# NRF.net
KiCad netlist of a schematic drawn in Altium Designer
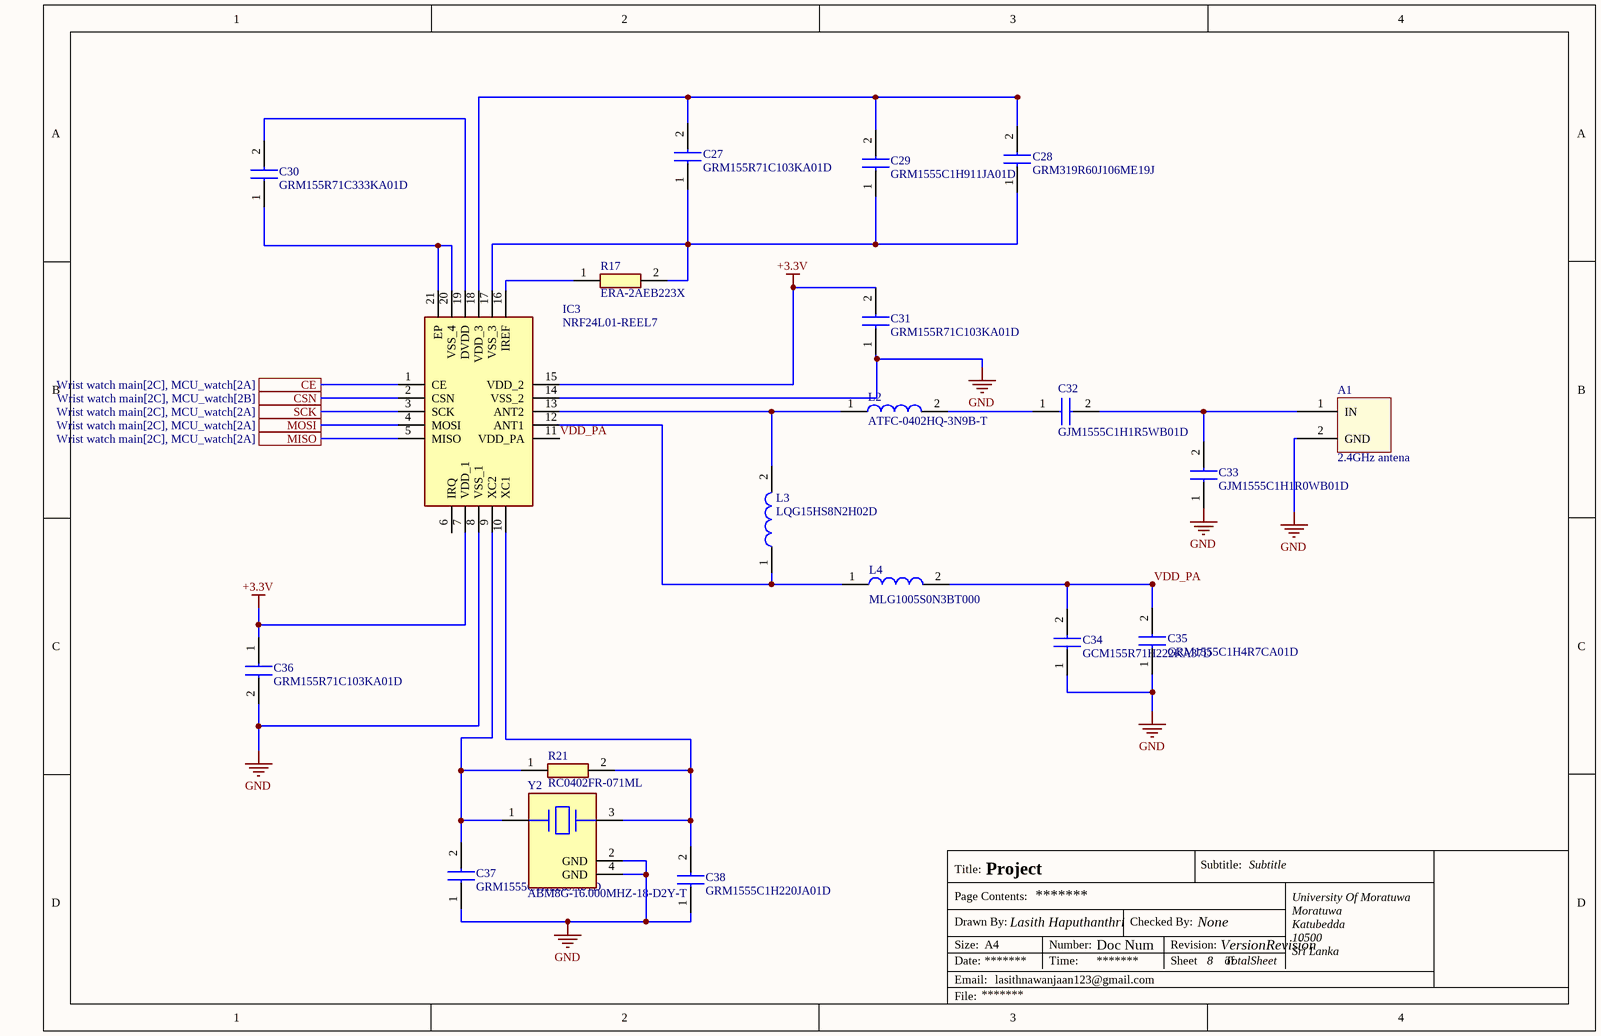
[diagram p0: NRF.SchDoc]

(export (version "E")
  (design (tool "Eeschema 10.0.6"))
  (components
    (comp (ref "A1")
      (value "2.4GHz antena")
      (footprint "Antena")
      (libsource (lib "Schlib1") (part "2.4GHz antena"))
    )
    (comp (ref "C27")
      (value "GRM155R71C103KA01D")
      (footprint "SamacSys:CAPC1005X55N")
      (description "Capacitor")
      (fields (field (name "MOUSER PART NUMBER") "81-GRM36X103K16"))
      (libsource (lib "*") (part "GRM155R71C103KA01D"))
    )
    (comp (ref "C28")
      (value "GRM319R60J106ME19J")
      (footprint "SamacSys:CAPC3216X95N")
      (description "Capacitor")
      (fields (field (name "MOUSER PART NUMBER") "81-GRM319R60J106ME9J"))
      (libsource (lib "*") (part "GRM319R60J106ME19J"))
    )
    (comp (ref "C29")
      (value "GRM1555C1H911JA01D")
      (footprint "SamacSys:CAPC1005X55N")
      (description "Capacitor")
      (fields (field (name "MOUSER PART NUMBER") "81-GRM1555C1H911JA1D"))
      (libsource (lib "*") (part "GRM1555C1H911JA01D"))
    )
    (comp (ref "C30")
      (value "GRM155R71C333KA01D")
      (footprint "SamacSys:CAPC1005X55N")
      (description "Capacitor")
      (libsource (lib "*") (part "GRM155R71C333KA01D"))
    )
    (comp (ref "C31")
      (value "GRM155R71C103KA01D")
      (footprint "SamacSys:CAPC1005X55N")
      (description "Capacitor")
      (fields (field (name "MOUSER PART NUMBER") "81-GRM36X103K16"))
      (libsource (lib "*") (part "GRM155R71C103KA01D"))
    )
    (comp (ref "C32")
      (value "GJM1555C1H1R5WB01D")
      (footprint "SamacSys:CAPC1005X55N")
      (description "Capacitor")
      (fields (field (name "MOUSER PART NUMBER") "81-GJM1555C1H1R5WB1D"))
      (libsource (lib "*") (part "GJM1555C1H1R5WB01D"))
    )
    (comp (ref "C33")
      (value "GJM1555C1H1R0WB01D")
      (footprint "SamacSys:CAPC1005X55N")
      (description "Capacitor")
      (fields (field (name "MOUSER PART NUMBER") "81-GJM1555C1H1R0WB1D"))
      (libsource (lib "*") (part "GJM1555C1H1R0WB01D"))
    )
    (comp (ref "C34")
      (value "GCM155R71H222KA37D")
      (footprint "SamacSys:CAPC1005X55N")
      (description "Capacitor")
      (fields (field (name "MOUSER PART NUMBER") "81-GCM155R71H222K37D"))
      (libsource (lib "*") (part "GCM155R71H222KA37D"))
    )
    (comp (ref "C35")
      (value "GRM1555C1H4R7CA01D")
      (footprint "SamacSys:CAPC1005X55N")
      (description "Capacitor")
      (fields (field (name "MOUSER PART NUMBER") "81-GRM1555C1H4R7CA1D"))
      (libsource (lib "*") (part "GRM1555C1H4R7CA01D"))
    )
    (comp (ref "C36")
      (value "GRM155R71C103KA01D")
      (footprint "SamacSys:CAPC1005X55N")
      (description "Capacitor")
      (fields (field (name "MOUSER PART NUMBER") "81-GRM36X103K16"))
      (libsource (lib "*") (part "GRM155R71C103KA01D"))
    )
    (comp (ref "C37")
      (value "GRM1555C1H220JA01D")
      (footprint "SamacSys:CAPC1005X55N")
      (description "Capacitor")
      (fields (field (name "MOUSER PART NUMBER") "81-GRM1555C1H220JA1D"))
      (libsource (lib "*") (part "GRM1555C1H220JA01D"))
    )
    (comp (ref "C38")
      (value "GRM1555C1H220JA01D")
      (footprint "SamacSys:CAPC1005X55N")
      (description "Capacitor")
      (fields (field (name "MOUSER PART NUMBER") "81-GRM1555C1H220JA1D"))
      (libsource (lib "*") (part "GRM1555C1H220JA01D"))
    )
    (comp (ref "IC3")
      (value "NRF24L01-REEL7")
      (footprint "SamacSys:QFN50P400X400X80-21N-D")
      (description "Integrated Circuit")
      (fields (field (name "MOUSER PART NUMBER") "949-NRF24L01-REEL7"))
      (libsource (lib "*") (part "NRF24L01-REEL7"))
    )
    (comp (ref "L2")
      (value "ATFC-0402HQ-3N9B-T")
      (footprint "SamacSys:INDC1005X37N")
      (description "Inductor")
      (libsource (lib "*") (part "ATFC-0402HQ-3N9B-T"))
    )
    (comp (ref "L3")
      (value "LQG15HS8N2H02D")
      (footprint "SamacSys:LQG15WH0N7B02D")
      (description "Inductor")
      (fields (field (name "MOUSER PART NUMBER") "81-LQG15HS8N2H02D"))
      (libsource (lib "*") (part "LQG15HS8N2H02D"))
    )
    (comp (ref "L4")
      (value "MLG1005S0N3BT000")
      (footprint "SamacSys:MLG1005")
      (description "Inductor")
      (fields (field (name "MOUSER PART NUMBER") "810-MLG1005S0N3BT000"))
      (libsource (lib "*") (part "MLG1005S0N3BT000"))
    )
    (comp (ref "R17")
      (value "ERA-2AEB223X")
      (footprint "SamacSys:ERA2AED122X")
      (description "Resistor")
      (fields (field (name "MOUSER PART NUMBER") "667-ERA-2AEB223X"))
      (libsource (lib "*") (part "ERA-2AEB223X"))
    )
    (comp (ref "R21")
      (value "RC0402FR-071ML")
      (footprint "SamacSys:RESC1005X40N")
      (description "Resistor")
      (fields (field (name "MOUSER PART NUMBER") "603-RC0402FR-071ML"))
      (libsource (lib "*") (part "RC0402FR-071ML"))
    )
    (comp (ref "Y2")
      (value "ABM8G-16.000MHZ-18-D2Y-T")
      (footprint "FP-ABM8G-MFG")
      (description "Crystal 12MHz ±20ppm (Tol) ±30ppm (Stability) 18pF FUND 120Ω 4-Pin SMD T/R")
      (fields (field (name "TOLERANCE") "20ppm"))
      (libsource (lib "Altium Content Vault") (part "48e526d86b7f2615d98721063c72f49"))
    )
  )
  (nets
    (net (code "1") (name "+3.3V") (class "Default")
      (node (ref "C31") (pin "2") (pinfunction "2_2") (pintype "passive"))
      (node (ref "C36") (pin "1") (pinfunction "1_1") (pintype "passive"))
      (node (ref "IC3") (pin "15") (pinfunction "VDD_2_15") (pintype "passive"))
      (node (ref "IC3") (pin "7") (pinfunction "VDD_1_7") (pintype "passive"))
    )
    (net (code "2") (name "/CE") (class "Default")
      (node (ref "IC3") (pin "1") (pinfunction "CE_1") (pintype "passive"))
    )
    (net (code "3") (name "/CSN") (class "Default")
      (node (ref "IC3") (pin "2") (pinfunction "CSN_2") (pintype "passive"))
    )
    (net (code "4") (name "/MISO") (class "Default")
      (node (ref "IC3") (pin "5") (pinfunction "MISO_5") (pintype "passive"))
    )
    (net (code "5") (name "/MOSI") (class "Default")
      (node (ref "IC3") (pin "4") (pinfunction "MOSI_4") (pintype "passive"))
    )
    (net (code "6") (name "/SCK") (class "Default")
      (node (ref "IC3") (pin "3") (pinfunction "SCK_3") (pintype "passive"))
    )
    (net (code "7") (name "/VDD_PA") (class "Default")
      (node (ref "C34") (pin "2") (pinfunction "2_2") (pintype "passive"))
      (node (ref "C35") (pin "2") (pinfunction "2_2") (pintype "passive"))
      (node (ref "IC3") (pin "11") (pinfunction "VDD_PA_11") (pintype "passive"))
      (node (ref "L4") (pin "2") (pinfunction "2_2") (pintype "passive"))
    )
    (net (code "8") (name "GND") (class "Default")
      (node (ref "A1") (pin "2") (pinfunction "GND_2") (pintype "passive"))
      (node (ref "C31") (pin "1") (pinfunction "1_1") (pintype "passive"))
      (node (ref "C33") (pin "1") (pinfunction "1_1") (pintype "passive"))
      (node (ref "C34") (pin "1") (pinfunction "1_1") (pintype "passive"))
      (node (ref "C35") (pin "1") (pinfunction "1_1") (pintype "passive"))
      (node (ref "C36") (pin "2") (pinfunction "2_2") (pintype "passive"))
      (node (ref "C37") (pin "1") (pinfunction "1_1") (pintype "passive"))
      (node (ref "C38") (pin "1") (pinfunction "1_1") (pintype "passive"))
      (node (ref "IC3") (pin "14") (pinfunction "VSS_2_14") (pintype "passive"))
      (node (ref "IC3") (pin "8") (pinfunction "VSS_1_8") (pintype "passive"))
      (node (ref "Y2") (pin "2") (pinfunction "GND_2") (pintype "power_in"))
      (node (ref "Y2") (pin "4") (pinfunction "GND_4") (pintype "power_in"))
    )
    (net (code "9") (name "Net-(A1-IN)") (class "Default")
      (node (ref "A1") (pin "1") (pinfunction "IN_1") (pintype "passive"))
      (node (ref "C32") (pin "2") (pinfunction "2_2") (pintype "passive"))
      (node (ref "C33") (pin "2") (pinfunction "2_2") (pintype "passive"))
    )
    (net (code "10") (name "Net-(C32-Pad1)") (class "Default")
      (node (ref "C32") (pin "1") (pinfunction "1_1") (pintype "passive"))
      (node (ref "L2") (pin "2") (pinfunction "2_2") (pintype "passive"))
    )
    (net (code "11") (name "Net-(IC3-ANT1)") (class "Default")
      (node (ref "IC3") (pin "12") (pinfunction "ANT1_12") (pintype "passive"))
      (node (ref "L3") (pin "1") (pinfunction "1_1") (pintype "passive"))
      (node (ref "L4") (pin "1") (pinfunction "1_1") (pintype "passive"))
    )
    (net (code "12") (name "Net-(IC3-ANT2)") (class "Default")
      (node (ref "IC3") (pin "13") (pinfunction "ANT2_13") (pintype "passive"))
      (node (ref "L2") (pin "1") (pinfunction "1_1") (pintype "passive"))
      (node (ref "L3") (pin "2") (pinfunction "2_2") (pintype "passive"))
    )
    (net (code "13") (name "Net-(IC3-DVDD)") (class "Default")
      (node (ref "C30") (pin "2") (pinfunction "2_2") (pintype "passive"))
      (node (ref "IC3") (pin "19") (pinfunction "DVDD_19") (pintype "passive"))
    )
    (net (code "14") (name "Net-(IC3-EP)") (class "Default")
      (node (ref "C30") (pin "1") (pinfunction "1_1") (pintype "passive"))
      (node (ref "IC3") (pin "20") (pinfunction "VSS_4_20") (pintype "passive"))
      (node (ref "IC3") (pin "21") (pinfunction "EP_21") (pintype "passive"))
    )
    (net (code "15") (name "Net-(IC3-IREF)") (class "Default")
      (node (ref "IC3") (pin "16") (pinfunction "IREF_16") (pintype "passive"))
      (node (ref "R17") (pin "1") (pinfunction "1_1") (pintype "passive"))
    )
    (net (code "16") (name "Net-(IC3-VDD_3)") (class "Default")
      (node (ref "C27") (pin "2") (pinfunction "2_2") (pintype "passive"))
      (node (ref "C28") (pin "2") (pinfunction "2_2") (pintype "passive"))
      (node (ref "C29") (pin "2") (pinfunction "2_2") (pintype "passive"))
      (node (ref "IC3") (pin "18") (pinfunction "VDD_3_18") (pintype "passive"))
    )
    (net (code "17") (name "Net-(IC3-VSS_3)") (class "Default")
      (node (ref "C27") (pin "1") (pinfunction "1_1") (pintype "passive"))
      (node (ref "C28") (pin "1") (pinfunction "1_1") (pintype "passive"))
      (node (ref "C29") (pin "1") (pinfunction "1_1") (pintype "passive"))
      (node (ref "IC3") (pin "17") (pinfunction "VSS_3_17") (pintype "passive"))
      (node (ref "R17") (pin "2") (pinfunction "2_2") (pintype "passive"))
    )
    (net (code "18") (name "Net-(IC3-XC1)") (class "Default")
      (node (ref "C38") (pin "2") (pinfunction "2_2") (pintype "passive"))
      (node (ref "IC3") (pin "10") (pinfunction "XC1_10") (pintype "passive"))
      (node (ref "R21") (pin "2") (pinfunction "2_2") (pintype "passive"))
      (node (ref "Y2") (pin "3") (pinfunction "3_3") (pintype "passive"))
    )
    (net (code "19") (name "Net-(IC3-XC2)") (class "Default")
      (node (ref "C37") (pin "2") (pinfunction "2_2") (pintype "passive"))
      (node (ref "IC3") (pin "9") (pinfunction "XC2_9") (pintype "passive"))
      (node (ref "R21") (pin "1") (pinfunction "1_1") (pintype "passive"))
      (node (ref "Y2") (pin "1") (pinfunction "1_1") (pintype "passive"))
    )
    (net (code "20") (name "unconnected-(IC3-IRQ-Pad6)") (class "Default")
      (node (ref "IC3") (pin "6") (pinfunction "IRQ_6") (pintype "passive"))
    )
  )
)
